# DemoCat.net
KiCad netlist of a schematic drawn in Altium Designer
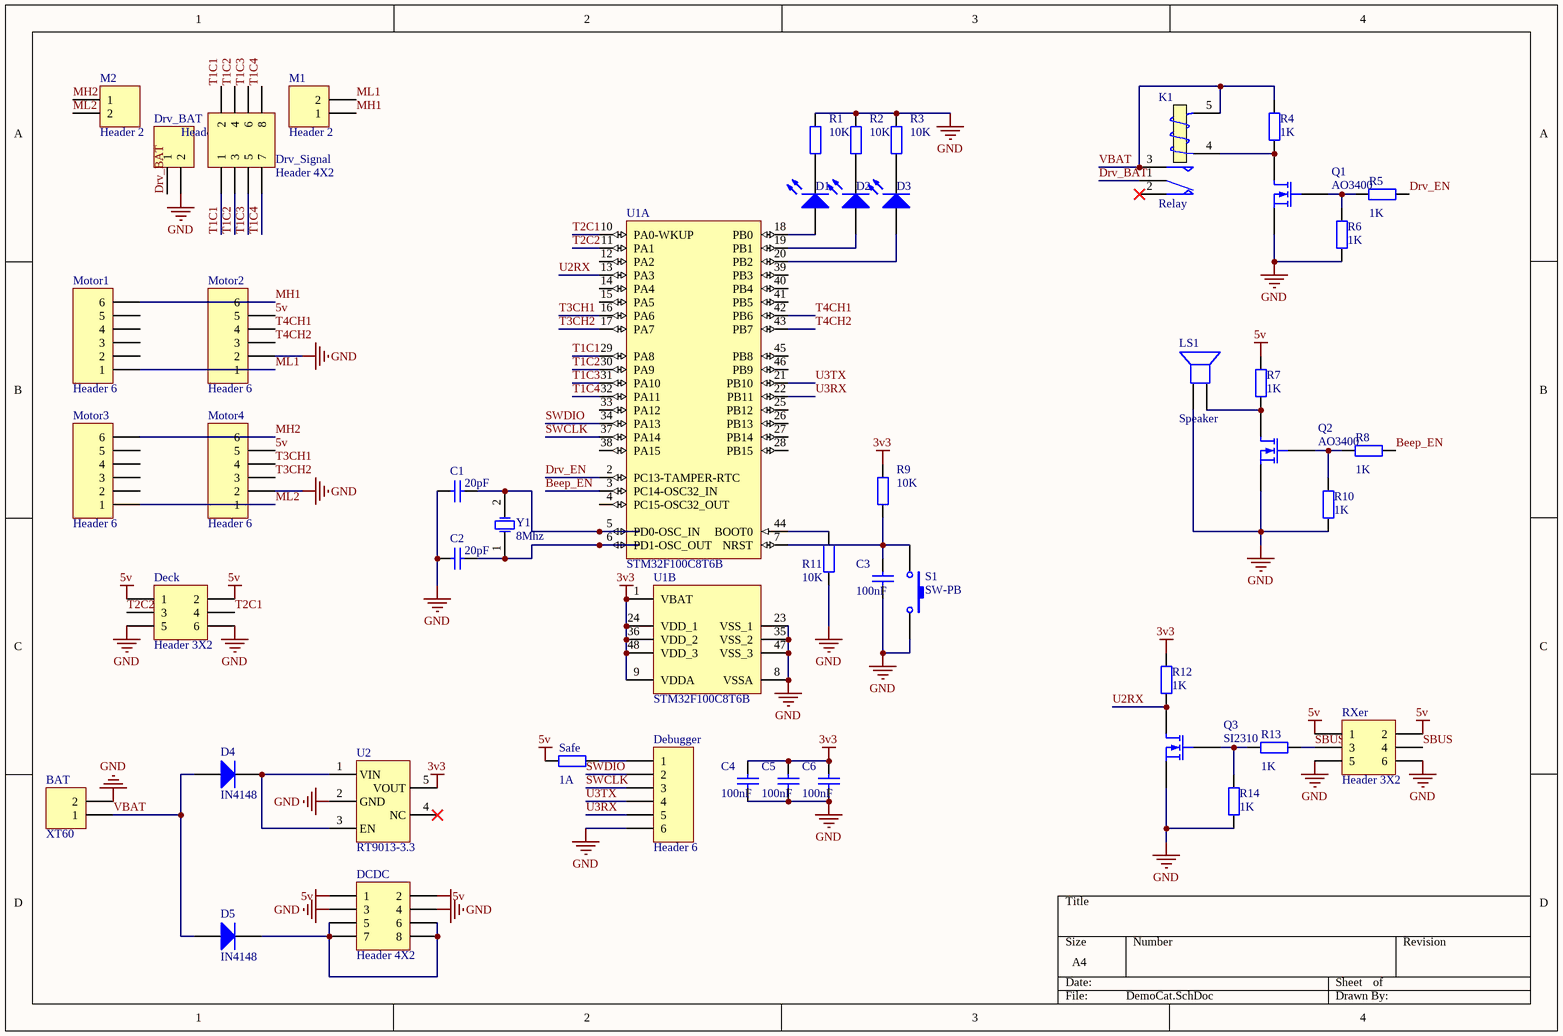
[diagram p0: DemoCat.SchDoc]

(export (version "E")
  (design (tool "Eeschema 10.0.6"))
  (components
    (comp (ref "BAT")
      (value "XT60")
      (footprint "XT30-IN-W")
      (description "Header, 2-Pin")
      (fields (field (name "PUBLISHER") "Altium Limited"))
      (libsource (lib "Miscellaneous Connectors") (part "Header 2"))
    )
    (comp (ref "C1")
      (value "20pF")
      (footprint "0603C")
      (description "Capacitor")
      (fields (field (name "Comment") "Cap") (field (name "PUBLISHER") "Altium Limited"))
      (libsource (lib "Miscellaneous Devices") (part "Cap"))
    )
    (comp (ref "C2")
      (value "20pF")
      (footprint "0603C")
      (description "Capacitor")
      (fields (field (name "Comment") "Cap") (field (name "PUBLISHER") "Altium Limited"))
      (libsource (lib "Miscellaneous Devices") (part "Cap"))
    )
    (comp (ref "C3")
      (value "100nF")
      (footprint "0603C")
      (description "Capacitor")
      (fields (field (name "Comment") "Cap") (field (name "PUBLISHER") "Altium Limited"))
      (libsource (lib "Miscellaneous Devices") (part "Cap"))
    )
    (comp (ref "C4")
      (value "100nF")
      (footprint "0603C")
      (description "Capacitor")
      (fields (field (name "Comment") "Cap") (field (name "PUBLISHER") "Altium Limited"))
      (libsource (lib "Miscellaneous Devices") (part "Cap"))
    )
    (comp (ref "C5")
      (value "100nF")
      (footprint "0603C")
      (description "Capacitor")
      (fields (field (name "Comment") "Cap") (field (name "PUBLISHER") "Altium Limited"))
      (libsource (lib "Miscellaneous Devices") (part "Cap"))
    )
    (comp (ref "C6")
      (value "100nF")
      (footprint "0603C")
      (description "Capacitor")
      (fields (field (name "Comment") "Cap") (field (name "PUBLISHER") "Altium Limited"))
      (libsource (lib "Miscellaneous Devices") (part "Cap"))
    )
    (comp (ref "D1")
      (value "LED0")
      (footprint "0603LED - Red")
      (description "Typical INFRARED GaAs LED")
      (fields (field (name "PUBLISHER") "Altium Limited"))
      (libsource (lib "Miscellaneous Devices") (part "LED0"))
    )
    (comp (ref "D2")
      (value "LED0")
      (footprint "0603LED - Green")
      (description "Typical INFRARED GaAs LED")
      (fields (field (name "PUBLISHER") "Altium Limited"))
      (libsource (lib "Miscellaneous Devices") (part "LED0"))
    )
    (comp (ref "D3")
      (value "LED0")
      (footprint "0603LED - Blue")
      (description "Typical INFRARED GaAs LED")
      (fields (field (name "PUBLISHER") "Altium Limited"))
      (libsource (lib "Miscellaneous Devices") (part "LED0"))
    )
    (comp (ref "D4")
      (value "IN4148")
      (footprint "DO-214AA(SMB)")
      (description "Default Diode")
      (fields (field (name "PUBLISHER") "Altium Limited"))
      (libsource (lib "Miscellaneous Devices") (part "Diode"))
    )
    (comp (ref "D5")
      (value "IN4148")
      (footprint "DO-214AA(SMB)")
      (description "Default Diode")
      (fields (field (name "PUBLISHER") "Altium Limited"))
      (libsource (lib "Miscellaneous Devices") (part "Diode"))
    )
    (comp (ref "DCDC")
      (value "Header 4X2")
      (footprint "HDR_SMT_2x4")
      (description "Header, 4-Pin, Dual row")
      (fields (field (name "PUBLISHER") "Altium Limited"))
      (libsource (lib "") (part "Header 4X2_1"))
    )
    (comp (ref "Debugger")
      (value "Header 6")
      (footprint "GX1.25_T_6P")
      (description "Header, 6-Pin")
      (fields (field (name "PUBLISHER") "Altium Limited"))
      (libsource (lib "") (part "Header 6_1"))
    )
    (comp (ref "Deck")
      (value "Header 3X2")
      (footprint "HDR_SMT_2x3")
      (description "Header, 3-Pin, Dual row")
      (fields (field (name "PUBLISHER") "Altium Limited"))
      (libsource (lib "Miscellaneous Connectors") (part "Header 3X2"))
    )
    (comp (ref "Drv_BAT")
      (value "Header 2")
      (footprint "XH2.54_2P_T")
      (description "Header, 2-Pin")
      (fields (field (name "PUBLISHER") "Altium Limited"))
      (libsource (lib "") (part "Header 2_2"))
    )
    (comp (ref "Drv_Signal")
      (value "Header 4X2")
      (footprint "HDR_SMT_2x4")
      (description "Header, 4-Pin, Dual row")
      (fields (field (name "PUBLISHER") "Altium Limited"))
      (libsource (lib "Miscellaneous Connectors") (part "Header 4X2"))
    )
    (comp (ref "K1")
      (value "Relay")
      (footprint "rl")
      (description "SPDT Relay")
      (fields (field (name "PUBLISHER") "Altium Limited"))
      (libsource (lib "Relay") (part "Relay"))
    )
    (comp (ref "LS1")
      (value "Speaker")
      (footprint "PIN2")
      (description "Loudspeaker")
      (fields (field (name "PUBLISHER") "Altium Limited"))
      (libsource (lib "Miscellaneous Devices") (part "Speaker"))
    )
    (comp (ref "M1")
      (value "Header 2")
      (footprint "XH2.54_2P_T")
      (description "Header, 2-Pin")
      (fields (field (name "PUBLISHER") "Altium Limited"))
      (libsource (lib "Miscellaneous Connectors") (part "Header 2"))
    )
    (comp (ref "M2")
      (value "Header 2")
      (footprint "XH2.54_2P_T")
      (description "Header, 2-Pin")
      (fields (field (name "PUBLISHER") "Altium Limited"))
      (libsource (lib "") (part "Header 2_1"))
    )
    (comp (ref "Motor1")
      (value "Header 6")
      (footprint "HDR_SMT_1x6")
      (description "Header, 6-Pin")
      (fields (field (name "PUBLISHER") "Altium Limited"))
      (libsource (lib "Miscellaneous Connectors") (part "Header 6"))
    )
    (comp (ref "Motor2")
      (value "Header 6")
      (footprint "HDR_SMT_1x6")
      (description "Header, 6-Pin")
      (fields (field (name "PUBLISHER") "Altium Limited"))
      (libsource (lib "Miscellaneous Connectors") (part "Header 6"))
    )
    (comp (ref "Motor3")
      (value "Header 6")
      (footprint "HDR_SMT_1x6")
      (description "Header, 6-Pin")
      (fields (field (name "PUBLISHER") "Altium Limited"))
      (libsource (lib "Miscellaneous Connectors") (part "Header 6"))
    )
    (comp (ref "Motor4")
      (value "Header 6")
      (footprint "HDR_SMT_1x6")
      (description "Header, 6-Pin")
      (fields (field (name "PUBLISHER") "Altium Limited"))
      (libsource (lib "Miscellaneous Connectors") (part "Header 6"))
    )
    (comp (ref "Q1")
      (value "AO3400")
      (footprint "SOT-23-MOS")
      (description "N-Channel MOSFET")
      (fields (field (name "PUBLISHER") "Altium Limited"))
      (libsource (lib "Miscellaneous Devices") (part "MOSFET-N"))
    )
    (comp (ref "Q2")
      (value "AO3400")
      (footprint "SOT-23-MOS")
      (description "N-Channel MOSFET")
      (fields (field (name "PUBLISHER") "Altium Limited"))
      (libsource (lib "Miscellaneous Devices") (part "MOSFET-N"))
    )
    (comp (ref "Q3")
      (value "SI2310")
      (footprint "SOT-23-MOS")
      (description "N-Channel MOSFET")
      (fields (field (name "PUBLISHER") "Altium Limited"))
      (libsource (lib "Miscellaneous Devices") (part "MOSFET-N"))
    )
    (comp (ref "R1")
      (value "10K")
      (footprint "0603R")
      (description "Resistor")
      (fields (field (name "PUBLISHER") "Altium Limited"))
      (libsource (lib "Miscellaneous Devices") (part "Res2"))
    )
    (comp (ref "R2")
      (value "10K")
      (footprint "0603R")
      (description "Resistor")
      (fields (field (name "PUBLISHER") "Altium Limited"))
      (libsource (lib "Miscellaneous Devices") (part "Res2"))
    )
    (comp (ref "R3")
      (value "10K")
      (footprint "0603R")
      (description "Resistor")
      (fields (field (name "PUBLISHER") "Altium Limited"))
      (libsource (lib "Miscellaneous Devices") (part "Res2"))
    )
    (comp (ref "R4")
      (value "1K")
      (footprint "0603R")
      (description "Resistor")
      (fields (field (name "Comment") "Res2") (field (name "PUBLISHER") "Altium Limited"))
      (libsource (lib "Miscellaneous Devices") (part "Res2"))
    )
    (comp (ref "R5")
      (value "1K")
      (footprint "0603R")
      (description "Resistor")
      (fields (field (name "Comment") "Res2") (field (name "PUBLISHER") "Altium Limited"))
      (libsource (lib "") (part "Res2_1"))
    )
    (comp (ref "R6")
      (value "1K")
      (footprint "0603R")
      (description "Resistor")
      (fields (field (name "Comment") "Res2") (field (name "PUBLISHER") "Altium Limited"))
      (libsource (lib "Miscellaneous Devices") (part "Res2"))
    )
    (comp (ref "R7")
      (value "1K")
      (footprint "0603R")
      (description "Resistor")
      (fields (field (name "Comment") "Res2") (field (name "PUBLISHER") "Altium Limited"))
      (libsource (lib "Miscellaneous Devices") (part "Res2"))
    )
    (comp (ref "R8")
      (value "1K")
      (footprint "0603R")
      (description "Resistor")
      (fields (field (name "Comment") "Res2") (field (name "PUBLISHER") "Altium Limited"))
      (libsource (lib "") (part "Res2_1"))
    )
    (comp (ref "R9")
      (value "10K")
      (footprint "0603R")
      (description "Resistor")
      (fields (field (name "PUBLISHER") "Altium Limited"))
      (libsource (lib "Miscellaneous Devices") (part "Res2"))
    )
    (comp (ref "R10")
      (value "1K")
      (footprint "0603R")
      (description "Resistor")
      (fields (field (name "Comment") "Res2") (field (name "PUBLISHER") "Altium Limited"))
      (libsource (lib "Miscellaneous Devices") (part "Res2"))
    )
    (comp (ref "R11")
      (value "10K")
      (footprint "0603R")
      (description "Resistor")
      (fields (field (name "Comment") "Res2") (field (name "PUBLISHER") "Altium Limited"))
      (libsource (lib "Miscellaneous Devices") (part "Res2"))
    )
    (comp (ref "R12")
      (value "1K")
      (footprint "0603R")
      (description "Resistor")
      (fields (field (name "Comment") "Res2") (field (name "PUBLISHER") "Altium Limited"))
      (libsource (lib "Miscellaneous Devices") (part "Res2"))
    )
    (comp (ref "R13")
      (value "1K")
      (footprint "0603R")
      (description "Resistor")
      (fields (field (name "Comment") "Res2") (field (name "PUBLISHER") "Altium Limited"))
      (libsource (lib "") (part "Res2_1"))
    )
    (comp (ref "R14")
      (value "1K")
      (footprint "0603R")
      (description "Resistor")
      (fields (field (name "Comment") "Res2") (field (name "PUBLISHER") "Altium Limited"))
      (libsource (lib "Miscellaneous Devices") (part "Res2"))
    )
    (comp (ref "RXer")
      (value "Header 3X2")
      (footprint "HDR_SMT_2x3")
      (description "Header, 3-Pin, Dual row")
      (fields (field (name "PUBLISHER") "Altium Limited"))
      (libsource (lib "Miscellaneous Connectors") (part "Header 3X2"))
    )
    (comp (ref "S1")
      (value "SW-PB")
      (footprint "KeySwitch-3X3")
      (description "Switch")
      (fields (field (name "PUBLISHER") "Altium Limited"))
      (libsource (lib "Miscellaneous Devices") (part "SW-PB"))
    )
    (comp (ref "Safe")
      (value "1A")
      (footprint "0603R")
      (description "Resistor")
      (fields (field (name "Comment") "Res2") (field (name "PUBLISHER") "Altium Limited"))
      (libsource (lib "") (part "Res2_1"))
    )
    (comp (ref "U1")
      (value "STM32F100C8T6B")
      (footprint "STM-LQFP48_N")
      (libsource (lib "STM32F1") (part "STM32F100C8T6B"))
    )
    (comp (ref "U2")
      (value "RT9013-3.3")
      (footprint "SOT-23-5")
      (description "3.3V 500mA")
      (libsource (lib "My_Library") (part "RT9013"))
    )
    (comp (ref "Y1")
      (value "8Mhz")
      (footprint "3225-CrystalOsclitor")
      (fields (field (name "PUBLISHER") "Altium Limited"))
      (libsource (lib "Miscellaneous Devices") (part "XTAL"))
    )
  )
  (nets
    (net (code "1") (name "/Beep_EN") (class "Default")
      (node (ref "R8") (pin "2") (pinfunction "2_2") (pintype "passive"))
      (node (ref "U1") (pin "3") (pinfunction "PC14-OSC32_IN_3") (pintype "bidirectional"))
    )
    (net (code "2") (name "/Drv_BAT") (class "Default")
      (node (ref "Drv_BAT") (pin "1") (pinfunction "1_1") (pintype "passive"))
      (node (ref "K1") (pin "1") (pinfunction "COM_1") (pintype "passive"))
    )
    (net (code "3") (name "/Drv_EN") (class "Default")
      (node (ref "R5") (pin "2") (pinfunction "2_2") (pintype "passive"))
      (node (ref "U1") (pin "2") (pinfunction "PC13-TAMPER-RTC_2") (pintype "bidirectional"))
    )
    (net (code "4") (name "/MH1") (class "Default")
      (node (ref "M1") (pin "1") (pinfunction "1_1") (pintype "passive"))
      (node (ref "Motor1") (pin "6") (pinfunction "6_6") (pintype "passive"))
      (node (ref "Motor2") (pin "6") (pinfunction "6_6") (pintype "passive"))
    )
    (net (code "5") (name "/MH2") (class "Default")
      (node (ref "M2") (pin "1") (pinfunction "1_1") (pintype "passive"))
      (node (ref "Motor3") (pin "6") (pinfunction "6_6") (pintype "passive"))
      (node (ref "Motor4") (pin "6") (pinfunction "6_6") (pintype "passive"))
    )
    (net (code "6") (name "/ML1") (class "Default")
      (node (ref "M1") (pin "2") (pinfunction "2_2") (pintype "passive"))
      (node (ref "Motor1") (pin "1") (pinfunction "1_1") (pintype "passive"))
      (node (ref "Motor2") (pin "1") (pinfunction "1_1") (pintype "passive"))
    )
    (net (code "7") (name "/ML2") (class "Default")
      (node (ref "M2") (pin "2") (pinfunction "2_2") (pintype "passive"))
      (node (ref "Motor3") (pin "1") (pinfunction "1_1") (pintype "passive"))
      (node (ref "Motor4") (pin "1") (pinfunction "1_1") (pintype "passive"))
    )
    (net (code "8") (name "/SBUS") (class "Default")
      (node (ref "R13") (pin "2") (pinfunction "2_2") (pintype "passive"))
      (node (ref "RXer") (pin "3") (pinfunction "3_3") (pintype "passive"))
      (node (ref "RXer") (pin "4") (pinfunction "4_4") (pintype "passive"))
    )
    (net (code "9") (name "/SWCLK") (class "Default")
      (node (ref "Debugger") (pin "3") (pinfunction "3_3") (pintype "passive"))
      (node (ref "U1") (pin "37") (pinfunction "PA14_37") (pintype "bidirectional"))
    )
    (net (code "10") (name "/SWDIO") (class "Default")
      (node (ref "Debugger") (pin "2") (pinfunction "2_2") (pintype "passive"))
      (node (ref "U1") (pin "34") (pinfunction "PA13_34") (pintype "bidirectional"))
    )
    (net (code "11") (name "/T1C1") (class "Default")
      (node (ref "Drv_Signal") (pin "1") (pinfunction "1_1") (pintype "passive"))
      (node (ref "Drv_Signal") (pin "2") (pinfunction "2_2") (pintype "passive"))
      (node (ref "U1") (pin "29") (pinfunction "PA8_29") (pintype "bidirectional"))
    )
    (net (code "12") (name "/T1C2") (class "Default")
      (node (ref "Drv_Signal") (pin "3") (pinfunction "3_3") (pintype "passive"))
      (node (ref "Drv_Signal") (pin "4") (pinfunction "4_4") (pintype "passive"))
      (node (ref "U1") (pin "30") (pinfunction "PA9_30") (pintype "bidirectional"))
    )
    (net (code "13") (name "/T1C3") (class "Default")
      (node (ref "Drv_Signal") (pin "5") (pinfunction "5_5") (pintype "passive"))
      (node (ref "Drv_Signal") (pin "6") (pinfunction "6_6") (pintype "passive"))
      (node (ref "U1") (pin "31") (pinfunction "PA10_31") (pintype "bidirectional"))
    )
    (net (code "14") (name "/T1C4") (class "Default")
      (node (ref "Drv_Signal") (pin "7") (pinfunction "7_7") (pintype "passive"))
      (node (ref "Drv_Signal") (pin "8") (pinfunction "8_8") (pintype "passive"))
      (node (ref "U1") (pin "32") (pinfunction "PA11_32") (pintype "bidirectional"))
    )
    (net (code "15") (name "/T2C1") (class "Default")
      (node (ref "Deck") (pin "4") (pinfunction "4_4") (pintype "passive"))
      (node (ref "U1") (pin "10") (pinfunction "PA0-WKUP_10") (pintype "bidirectional"))
    )
    (net (code "16") (name "/T2C2") (class "Default")
      (node (ref "Deck") (pin "3") (pinfunction "3_3") (pintype "passive"))
      (node (ref "U1") (pin "11") (pinfunction "PA1_11") (pintype "bidirectional"))
    )
    (net (code "17") (name "/T3CH1") (class "Default")
      (node (ref "Motor4") (pin "4") (pinfunction "4_4") (pintype "passive"))
      (node (ref "U1") (pin "16") (pinfunction "PA6_16") (pintype "bidirectional"))
    )
    (net (code "18") (name "/T3CH2") (class "Default")
      (node (ref "Motor4") (pin "3") (pinfunction "3_3") (pintype "passive"))
      (node (ref "U1") (pin "17") (pinfunction "PA7_17") (pintype "bidirectional"))
    )
    (net (code "19") (name "/T4CH1") (class "Default")
      (node (ref "Motor2") (pin "4") (pinfunction "4_4") (pintype "passive"))
      (node (ref "U1") (pin "42") (pinfunction "PB6_42") (pintype "bidirectional"))
    )
    (net (code "20") (name "/T4CH2") (class "Default")
      (node (ref "Motor2") (pin "3") (pinfunction "3_3") (pintype "passive"))
      (node (ref "U1") (pin "43") (pinfunction "PB7_43") (pintype "bidirectional"))
    )
    (net (code "21") (name "/U2RX") (class "Default")
      (node (ref "Q3") (pin "1") (pinfunction "D_1") (pintype "passive"))
      (node (ref "R12") (pin "1") (pinfunction "1_1") (pintype "passive"))
      (node (ref "U1") (pin "13") (pinfunction "PA3_13") (pintype "bidirectional"))
    )
    (net (code "22") (name "/U3RX") (class "Default")
      (node (ref "Debugger") (pin "5") (pinfunction "5_5") (pintype "passive"))
      (node (ref "U1") (pin "22") (pinfunction "PB11_22") (pintype "bidirectional"))
    )
    (net (code "23") (name "/U3TX") (class "Default")
      (node (ref "Debugger") (pin "4") (pinfunction "4_4") (pintype "passive"))
      (node (ref "U1") (pin "21") (pinfunction "PB10_21") (pintype "bidirectional"))
    )
    (net (code "24") (name "/VBAT") (class "Default")
      (node (ref "BAT") (pin "1") (pinfunction "1_1") (pintype "passive"))
      (node (ref "D4") (pin "1") (pinfunction "A_1") (pintype "passive"))
      (node (ref "D5") (pin "1") (pinfunction "A_1") (pintype "passive"))
      (node (ref "K1") (pin "3") (pinfunction "NO_3") (pintype "passive"))
      (node (ref "K1") (pin "5") (pinfunction "T2_5") (pintype "passive"))
      (node (ref "R4") (pin "2") (pinfunction "2_2") (pintype "passive"))
    )
    (net (code "25") (name "3v3") (class "Default")
      (node (ref "C4") (pin "2") (pinfunction "2_2") (pintype "passive"))
      (node (ref "C5") (pin "2") (pinfunction "2_2") (pintype "passive"))
      (node (ref "C6") (pin "2") (pinfunction "2_2") (pintype "passive"))
      (node (ref "R12") (pin "2") (pinfunction "2_2") (pintype "passive"))
      (node (ref "R9") (pin "2") (pinfunction "2_2") (pintype "passive"))
      (node (ref "U1") (pin "1") (pinfunction "VBAT_1") (pintype "power_in"))
      (node (ref "U1") (pin "24") (pinfunction "VDD_1_24") (pintype "power_in"))
      (node (ref "U1") (pin "36") (pinfunction "VDD_2_36") (pintype "power_in"))
      (node (ref "U1") (pin "48") (pinfunction "VDD_3_48") (pintype "power_in"))
      (node (ref "U1") (pin "9") (pinfunction "VDDA_9") (pintype "power_in"))
      (node (ref "U2") (pin "5") (pinfunction "VOUT_5") (pintype "passive"))
    )
    (net (code "26") (name "5v") (class "Default")
      (node (ref "DCDC") (pin "1") (pinfunction "1_1") (pintype "passive"))
      (node (ref "DCDC") (pin "2") (pinfunction "2_2") (pintype "passive"))
      (node (ref "Deck") (pin "1") (pinfunction "1_1") (pintype "passive"))
      (node (ref "Deck") (pin "2") (pinfunction "2_2") (pintype "passive"))
      (node (ref "Motor2") (pin "5") (pinfunction "5_5") (pintype "passive"))
      (node (ref "Motor4") (pin "5") (pinfunction "5_5") (pintype "passive"))
      (node (ref "R7") (pin "2") (pinfunction "2_2") (pintype "passive"))
      (node (ref "RXer") (pin "1") (pinfunction "1_1") (pintype "passive"))
      (node (ref "RXer") (pin "2") (pinfunction "2_2") (pintype "passive"))
      (node (ref "Safe") (pin "1") (pinfunction "1_1") (pintype "passive"))
    )
    (net (code "27") (name "GND") (class "Default")
      (node (ref "BAT") (pin "2") (pinfunction "2_2") (pintype "passive"))
      (node (ref "C1") (pin "1") (pinfunction "1_1") (pintype "passive"))
      (node (ref "C2") (pin "1") (pinfunction "1_1") (pintype "passive"))
      (node (ref "C3") (pin "1") (pinfunction "1_1") (pintype "passive"))
      (node (ref "C4") (pin "1") (pinfunction "1_1") (pintype "passive"))
      (node (ref "C5") (pin "1") (pinfunction "1_1") (pintype "passive"))
      (node (ref "C6") (pin "1") (pinfunction "1_1") (pintype "passive"))
      (node (ref "DCDC") (pin "3") (pinfunction "3_3") (pintype "passive"))
      (node (ref "DCDC") (pin "4") (pinfunction "4_4") (pintype "passive"))
      (node (ref "Debugger") (pin "6") (pinfunction "6_6") (pintype "passive"))
      (node (ref "Deck") (pin "5") (pinfunction "5_5") (pintype "passive"))
      (node (ref "Deck") (pin "6") (pinfunction "6_6") (pintype "passive"))
      (node (ref "Drv_BAT") (pin "2") (pinfunction "2_2") (pintype "passive"))
      (node (ref "LS1") (pin "1") (pinfunction "1_1") (pintype "passive"))
      (node (ref "Motor2") (pin "2") (pinfunction "2_2") (pintype "passive"))
      (node (ref "Motor4") (pin "2") (pinfunction "2_2") (pintype "passive"))
      (node (ref "Q1") (pin "3") (pinfunction "S_3") (pintype "passive"))
      (node (ref "Q2") (pin "3") (pinfunction "S_3") (pintype "passive"))
      (node (ref "Q3") (pin "3") (pinfunction "S_3") (pintype "passive"))
      (node (ref "R1") (pin "2") (pinfunction "2_2") (pintype "passive"))
      (node (ref "R10") (pin "1") (pinfunction "1_1") (pintype "passive"))
      (node (ref "R11") (pin "1") (pinfunction "1_1") (pintype "passive"))
      (node (ref "R14") (pin "1") (pinfunction "1_1") (pintype "passive"))
      (node (ref "R2") (pin "2") (pinfunction "2_2") (pintype "passive"))
      (node (ref "R3") (pin "2") (pinfunction "2_2") (pintype "passive"))
      (node (ref "R6") (pin "1") (pinfunction "1_1") (pintype "passive"))
      (node (ref "RXer") (pin "5") (pinfunction "5_5") (pintype "passive"))
      (node (ref "RXer") (pin "6") (pinfunction "6_6") (pintype "passive"))
      (node (ref "S1") (pin "2") (pinfunction "2_2") (pintype "passive"))
      (node (ref "U1") (pin "23") (pinfunction "VSS_1_23") (pintype "power_in"))
      (node (ref "U1") (pin "35") (pinfunction "VSS_2_35") (pintype "power_in"))
      (node (ref "U1") (pin "47") (pinfunction "VSS_3_47") (pintype "power_in"))
      (node (ref "U1") (pin "8") (pinfunction "VSSA_8") (pintype "power_in"))
      (node (ref "U2") (pin "2") (pinfunction "GND_2") (pintype "passive"))
    )
    (net (code "28") (name "Net-(D1-A)") (class "Default")
      (node (ref "D1") (pin "1") (pinfunction "A_1") (pintype "passive"))
      (node (ref "U1") (pin "18") (pinfunction "PB0_18") (pintype "bidirectional"))
    )
    (net (code "29") (name "Net-(D1-K)") (class "Default")
      (node (ref "D1") (pin "2") (pinfunction "K_2") (pintype "passive"))
      (node (ref "R1") (pin "1") (pinfunction "1_1") (pintype "passive"))
    )
    (net (code "30") (name "Net-(D2-A)") (class "Default")
      (node (ref "D2") (pin "1") (pinfunction "A_1") (pintype "passive"))
      (node (ref "U1") (pin "19") (pinfunction "PB1_19") (pintype "bidirectional"))
    )
    (net (code "31") (name "Net-(D2-K)") (class "Default")
      (node (ref "D2") (pin "2") (pinfunction "K_2") (pintype "passive"))
      (node (ref "R2") (pin "1") (pinfunction "1_1") (pintype "passive"))
    )
    (net (code "32") (name "Net-(D3-A)") (class "Default")
      (node (ref "D3") (pin "1") (pinfunction "A_1") (pintype "passive"))
      (node (ref "U1") (pin "20") (pinfunction "PB2_20") (pintype "bidirectional"))
    )
    (net (code "33") (name "Net-(D3-K)") (class "Default")
      (node (ref "D3") (pin "2") (pinfunction "K_2") (pintype "passive"))
      (node (ref "R3") (pin "1") (pinfunction "1_1") (pintype "passive"))
    )
    (net (code "34") (name "Net-(D4-K)") (class "Default")
      (node (ref "D4") (pin "2") (pinfunction "K_2") (pintype "passive"))
      (node (ref "U2") (pin "1") (pinfunction "VIN_1") (pintype "passive"))
      (node (ref "U2") (pin "3") (pinfunction "EN_3") (pintype "passive"))
    )
    (net (code "35") (name "Net-(D5-K)") (class "Default")
      (node (ref "D5") (pin "2") (pinfunction "K_2") (pintype "passive"))
      (node (ref "DCDC") (pin "5") (pinfunction "5_5") (pintype "passive"))
      (node (ref "DCDC") (pin "6") (pinfunction "6_6") (pintype "passive"))
      (node (ref "DCDC") (pin "7") (pinfunction "7_7") (pintype "passive"))
      (node (ref "DCDC") (pin "8") (pinfunction "8_8") (pintype "passive"))
    )
    (net (code "36") (name "Net-(Debugger-Pad1)") (class "Default")
      (node (ref "Debugger") (pin "1") (pinfunction "1_1") (pintype "passive"))
      (node (ref "Safe") (pin "2") (pinfunction "2_2") (pintype "passive"))
    )
    (net (code "37") (name "Net-(K1-T1)") (class "Default")
      (node (ref "K1") (pin "4") (pinfunction "T1_4") (pintype "passive"))
      (node (ref "Q1") (pin "1") (pinfunction "D_1") (pintype "passive"))
      (node (ref "R4") (pin "1") (pinfunction "1_1") (pintype "passive"))
    )
    (net (code "38") (name "Net-(Q1-G)") (class "Default")
      (node (ref "Q1") (pin "2") (pinfunction "G_2") (pintype "passive"))
      (node (ref "R5") (pin "1") (pinfunction "1_1") (pintype "passive"))
      (node (ref "R6") (pin "2") (pinfunction "2_2") (pintype "passive"))
    )
    (net (code "39") (name "Net-(Q2-D)") (class "Default")
      (node (ref "LS1") (pin "2") (pinfunction "2_2") (pintype "passive"))
      (node (ref "Q2") (pin "1") (pinfunction "D_1") (pintype "passive"))
      (node (ref "R7") (pin "1") (pinfunction "1_1") (pintype "passive"))
    )
    (net (code "40") (name "Net-(Q2-G)") (class "Default")
      (node (ref "Q2") (pin "2") (pinfunction "G_2") (pintype "passive"))
      (node (ref "R10") (pin "2") (pinfunction "2_2") (pintype "passive"))
      (node (ref "R8") (pin "1") (pinfunction "1_1") (pintype "passive"))
    )
    (net (code "41") (name "Net-(Q3-G)") (class "Default")
      (node (ref "Q3") (pin "2") (pinfunction "G_2") (pintype "passive"))
      (node (ref "R13") (pin "1") (pinfunction "1_1") (pintype "passive"))
      (node (ref "R14") (pin "2") (pinfunction "2_2") (pintype "passive"))
    )
    (net (code "42") (name "Net-(U1A-BOOT0)") (class "Default")
      (node (ref "R11") (pin "2") (pinfunction "2_2") (pintype "passive"))
      (node (ref "U1") (pin "44") (pinfunction "BOOT0_44") (pintype "input"))
    )
    (net (code "43") (name "Net-(U1A-NRST)") (class "Default")
      (node (ref "C3") (pin "2") (pinfunction "2_2") (pintype "passive"))
      (node (ref "R9") (pin "1") (pinfunction "1_1") (pintype "passive"))
      (node (ref "S1") (pin "1") (pinfunction "1_1") (pintype "passive"))
      (node (ref "U1") (pin "7") (pinfunction "NRST_7") (pintype "bidirectional"))
    )
    (net (code "44") (name "Net-(U1A-PD0-OSC_IN)") (class "Default")
      (node (ref "C1") (pin "2") (pinfunction "2_2") (pintype "passive"))
      (node (ref "U1") (pin "5") (pinfunction "PD0-OSC_IN_5") (pintype "bidirectional"))
      (node (ref "Y1") (pin "2") (pinfunction "OSC2_2") (pintype "passive"))
    )
    (net (code "45") (name "Net-(U1A-PD1-OSC_OUT)") (class "Default")
      (node (ref "C2") (pin "2") (pinfunction "2_2") (pintype "passive"))
      (node (ref "U1") (pin "6") (pinfunction "PD1-OSC_OUT_6") (pintype "bidirectional"))
      (node (ref "Y1") (pin "1") (pinfunction "OSC1_1") (pintype "passive"))
    )
    (net (code "46") (name "unconnected-(K1-NC-Pad2)") (class "Default")
      (node (ref "K1") (pin "2") (pinfunction "NC_2") (pintype "passive+no_connect"))
    )
    (net (code "47") (name "unconnected-(Motor1-Pad2)") (class "Default")
      (node (ref "Motor1") (pin "2") (pinfunction "2_2") (pintype "passive"))
    )
    (net (code "48") (name "unconnected-(Motor1-Pad3)") (class "Default")
      (node (ref "Motor1") (pin "3") (pinfunction "3_3") (pintype "passive"))
    )
    (net (code "49") (name "unconnected-(Motor1-Pad4)") (class "Default")
      (node (ref "Motor1") (pin "4") (pinfunction "4_4") (pintype "passive"))
    )
    (net (code "50") (name "unconnected-(Motor1-Pad5)") (class "Default")
      (node (ref "Motor1") (pin "5") (pinfunction "5_5") (pintype "passive"))
    )
    (net (code "51") (name "unconnected-(Motor3-Pad2)") (class "Default")
      (node (ref "Motor3") (pin "2") (pinfunction "2_2") (pintype "passive"))
    )
    (net (code "52") (name "unconnected-(Motor3-Pad3)") (class "Default")
      (node (ref "Motor3") (pin "3") (pinfunction "3_3") (pintype "passive"))
    )
    (net (code "53") (name "unconnected-(Motor3-Pad4)") (class "Default")
      (node (ref "Motor3") (pin "4") (pinfunction "4_4") (pintype "passive"))
    )
    (net (code "54") (name "unconnected-(Motor3-Pad5)") (class "Default")
      (node (ref "Motor3") (pin "5") (pinfunction "5_5") (pintype "passive"))
    )
    (net (code "55") (name "unconnected-(U1A-PA2-Pad12)") (class "Default")
      (node (ref "U1") (pin "12") (pinfunction "PA2_12") (pintype "bidirectional"))
    )
    (net (code "56") (name "unconnected-(U1A-PA4-Pad14)") (class "Default")
      (node (ref "U1") (pin "14") (pinfunction "PA4_14") (pintype "bidirectional"))
    )
    (net (code "57") (name "unconnected-(U1A-PA5-Pad15)") (class "Default")
      (node (ref "U1") (pin "15") (pinfunction "PA5_15") (pintype "bidirectional"))
    )
    (net (code "58") (name "unconnected-(U1A-PA12-Pad33)") (class "Default")
      (node (ref "U1") (pin "33") (pinfunction "PA12_33") (pintype "bidirectional"))
    )
    (net (code "59") (name "unconnected-(U1A-PA15-Pad38)") (class "Default")
      (node (ref "U1") (pin "38") (pinfunction "PA15_38") (pintype "bidirectional"))
    )
    (net (code "60") (name "unconnected-(U1A-PB3-Pad39)") (class "Default")
      (node (ref "U1") (pin "39") (pinfunction "PB3_39") (pintype "bidirectional"))
    )
    (net (code "61") (name "unconnected-(U1A-PB4-Pad40)") (class "Default")
      (node (ref "U1") (pin "40") (pinfunction "PB4_40") (pintype "bidirectional"))
    )
    (net (code "62") (name "unconnected-(U1A-PB5-Pad41)") (class "Default")
      (node (ref "U1") (pin "41") (pinfunction "PB5_41") (pintype "bidirectional"))
    )
    (net (code "63") (name "unconnected-(U1A-PB8-Pad45)") (class "Default")
      (node (ref "U1") (pin "45") (pinfunction "PB8_45") (pintype "bidirectional"))
    )
    (net (code "64") (name "unconnected-(U1A-PB9-Pad46)") (class "Default")
      (node (ref "U1") (pin "46") (pinfunction "PB9_46") (pintype "bidirectional"))
    )
    (net (code "65") (name "unconnected-(U1A-PB12-Pad25)") (class "Default")
      (node (ref "U1") (pin "25") (pinfunction "PB12_25") (pintype "bidirectional"))
    )
    (net (code "66") (name "unconnected-(U1A-PB13-Pad26)") (class "Default")
      (node (ref "U1") (pin "26") (pinfunction "PB13_26") (pintype "bidirectional"))
    )
    (net (code "67") (name "unconnected-(U1A-PB14-Pad27)") (class "Default")
      (node (ref "U1") (pin "27") (pinfunction "PB14_27") (pintype "bidirectional"))
    )
    (net (code "68") (name "unconnected-(U1A-PB15-Pad28)") (class "Default")
      (node (ref "U1") (pin "28") (pinfunction "PB15_28") (pintype "bidirectional"))
    )
    (net (code "69") (name "unconnected-(U1A-PC15-OSC32_OUT-Pad4)") (class "Default")
      (node (ref "U1") (pin "4") (pinfunction "PC15-OSC32_OUT_4") (pintype "bidirectional"))
    )
    (net (code "70") (name "unconnected-(U2-NC-Pad4)") (class "Default")
      (node (ref "U2") (pin "4") (pinfunction "NC_4") (pintype "passive+no_connect"))
    )
  )
)
